# programador.net
KiCad netlist of a schematic drawn in EAGLE
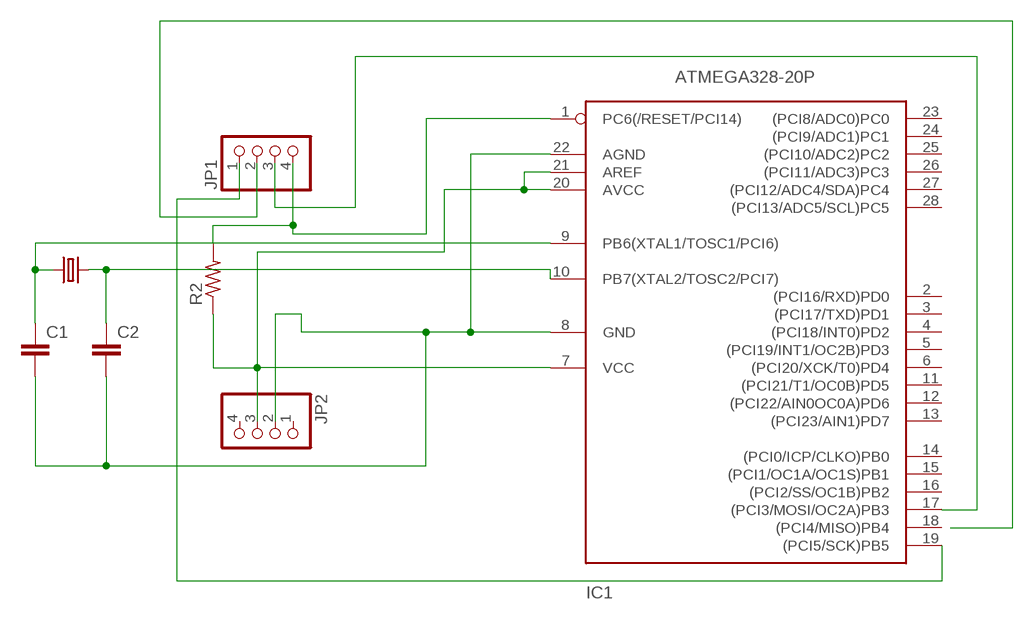
[diagram p0: schematic, sheet 1]

(export (version "E")
  (design (tool "Eeschema 10.0.6"))
  (components
    (comp (ref "C1")
      (value "C5/3.5")
      (footprint "eagle-import:C5B3.5")
      (libsource (lib "eagle-import") (part "C5/3.5"))
    )
    (comp (ref "C2")
      (value "C5/3.5")
      (footprint "eagle-import:C5B3.5")
      (libsource (lib "eagle-import") (part "C5/3.5"))
    )
    (comp (ref "IC1")
      (value "ATMEGA328-20P")
      (footprint "eagle-import:DIL28-3")
      (libsource (lib "eagle-import") (part "ATMEGA328P-20"))
    )
    (comp (ref "JP1")
      (value "PINHD-1X4")
      (footprint "eagle-import:1X04")
      (libsource (lib "eagle-import") (part "PINHD-1X4"))
    )
    (comp (ref "JP2")
      (value "PINHD-1X4")
      (footprint "eagle-import:1X04")
      (libsource (lib "eagle-import") (part "PINHD-1X4"))
    )
    (comp (ref "Q1")
      (value "CRYSTALHC49S")
      (footprint "eagle-import:HC49_S")
      (libsource (lib "eagle-import") (part "CRYSTALHC49S"))
    )
    (comp (ref "R2")
      (value "R-US_0207/10")
      (footprint "eagle-import:0207_10")
      (libsource (lib "eagle-import") (part "R-US_0207/10"))
    )
  )
  (nets
    (net (code "1") (name "Net-(IC1-(PCI3{slash}MOSI{slash}OC2A)PB3)") (class "Default")
      (node (ref "IC1") (pin "17") (pinfunction "(PCI3/MOSI/OC2A)PB3_17") (pintype "bidirectional"))
      (node (ref "JP1") (pin "3") (pinfunction "3_3") (pintype "passive"))
    )
    (net (code "2") (name "Net-(IC1-(PCI5{slash}SCK)PB5)") (class "Default")
      (node (ref "IC1") (pin "19") (pinfunction "(PCI5/SCK)PB5_19") (pintype "bidirectional"))
      (node (ref "JP1") (pin "1") (pinfunction "1_1") (pintype "passive"))
    )
    (net (code "3") (name "Net-(IC1-AGND)") (class "Default")
      (node (ref "C1") (pin "2") (pinfunction "2_2") (pintype "passive"))
      (node (ref "C2") (pin "2") (pinfunction "2_2") (pintype "passive"))
      (node (ref "IC1") (pin "22") (pinfunction "AGND_22") (pintype "bidirectional"))
      (node (ref "IC1") (pin "8") (pinfunction "GND_8") (pintype "bidirectional"))
      (node (ref "JP2") (pin "2") (pinfunction "2_2") (pintype "passive"))
    )
    (net (code "4") (name "Net-(IC1-AREF)") (class "Default")
      (node (ref "IC1") (pin "20") (pinfunction "AVCC_20") (pintype "bidirectional"))
      (node (ref "IC1") (pin "21") (pinfunction "AREF_21") (pintype "bidirectional"))
      (node (ref "IC1") (pin "7") (pinfunction "VCC_7") (pintype "bidirectional"))
      (node (ref "JP2") (pin "3") (pinfunction "3_3") (pintype "passive"))
      (node (ref "R2") (pin "1") (pinfunction "1_1") (pintype "passive"))
    )
    (net (code "5") (name "Net-(IC1-PB6(XTAL1{slash}TOSC1{slash}PCI6))") (class "Default")
      (node (ref "C1") (pin "1") (pinfunction "1_1") (pintype "passive"))
      (node (ref "IC1") (pin "9") (pinfunction "PB6(XTAL1/TOSC1/PCI6)_9") (pintype "bidirectional"))
      (node (ref "Q1") (pin "1") (pinfunction "1_1") (pintype "passive"))
    )
    (net (code "6") (name "Net-(IC1-PB7(XTAL2{slash}TOSC2{slash}PCI7))") (class "Default")
      (node (ref "C2") (pin "1") (pinfunction "1_1") (pintype "passive"))
      (node (ref "IC1") (pin "10") (pinfunction "PB7(XTAL2/TOSC2/PCI7)_10") (pintype "bidirectional"))
      (node (ref "Q1") (pin "2") (pinfunction "2_2") (pintype "passive"))
    )
    (net (code "7") (name "Net-(IC1-PC6({slash}RESET{slash}PCI14))") (class "Default")
      (node (ref "IC1") (pin "1") (pinfunction "PC6(/RESET/PCI14)_1") (pintype "bidirectional"))
      (node (ref "JP1") (pin "4") (pinfunction "4_4") (pintype "passive"))
      (node (ref "R2") (pin "2") (pinfunction "2_2") (pintype "passive"))
    )
    (net (code "8") (name "unconnected-(IC1-(PCI0{slash}ICP{slash}CLKO)PB0-Pad14)") (class "Default")
      (node (ref "IC1") (pin "14") (pinfunction "(PCI0/ICP/CLKO)PB0_14") (pintype "bidirectional"))
    )
    (net (code "9") (name "unconnected-(IC1-(PCI1{slash}OC1A{slash}OC1S)PB1-Pad15)") (class "Default")
      (node (ref "IC1") (pin "15") (pinfunction "(PCI1/OC1A/OC1S)PB1_15") (pintype "bidirectional"))
    )
    (net (code "10") (name "unconnected-(IC1-(PCI2{slash}SS{slash}OC1B)PB2-Pad16)") (class "Default")
      (node (ref "IC1") (pin "16") (pinfunction "(PCI2/SS/OC1B)PB2_16") (pintype "bidirectional"))
    )
    (net (code "11") (name "unconnected-(IC1-(PCI4{slash}MISO)PB4-Pad18)") (class "Default")
      (node (ref "IC1") (pin "18") (pinfunction "(PCI4/MISO)PB4_18") (pintype "bidirectional"))
    )
    (net (code "12") (name "unconnected-(IC1-(PCI8{slash}ADC0)PC0-Pad23)") (class "Default")
      (node (ref "IC1") (pin "23") (pinfunction "(PCI8/ADC0)PC0_23") (pintype "bidirectional"))
    )
    (net (code "13") (name "unconnected-(IC1-(PCI9{slash}ADC1)PC1-Pad24)") (class "Default")
      (node (ref "IC1") (pin "24") (pinfunction "(PCI9/ADC1)PC1_24") (pintype "bidirectional"))
    )
    (net (code "14") (name "unconnected-(IC1-(PCI10{slash}ADC2)PC2-Pad25)") (class "Default")
      (node (ref "IC1") (pin "25") (pinfunction "(PCI10/ADC2)PC2_25") (pintype "bidirectional"))
    )
    (net (code "15") (name "unconnected-(IC1-(PCI11{slash}ADC3)PC3-Pad26)") (class "Default")
      (node (ref "IC1") (pin "26") (pinfunction "(PCI11/ADC3)PC3_26") (pintype "bidirectional"))
    )
    (net (code "16") (name "unconnected-(IC1-(PCI12{slash}ADC4{slash}SDA)PC4-Pad27)") (class "Default")
      (node (ref "IC1") (pin "27") (pinfunction "(PCI12/ADC4/SDA)PC4_27") (pintype "bidirectional"))
    )
    (net (code "17") (name "unconnected-(IC1-(PCI13{slash}ADC5{slash}SCL)PC5-Pad28)") (class "Default")
      (node (ref "IC1") (pin "28") (pinfunction "(PCI13/ADC5/SCL)PC5_28") (pintype "bidirectional"))
    )
    (net (code "18") (name "unconnected-(IC1-(PCI16{slash}RXD)PD0-Pad2)") (class "Default")
      (node (ref "IC1") (pin "2") (pinfunction "(PCI16/RXD)PD0_2") (pintype "bidirectional"))
    )
    (net (code "19") (name "unconnected-(IC1-(PCI17{slash}TXD)PD1-Pad3)") (class "Default")
      (node (ref "IC1") (pin "3") (pinfunction "(PCI17/TXD)PD1_3") (pintype "bidirectional"))
    )
    (net (code "20") (name "unconnected-(IC1-(PCI18{slash}INT0)PD2-Pad4)") (class "Default")
      (node (ref "IC1") (pin "4") (pinfunction "(PCI18/INT0)PD2_4") (pintype "bidirectional"))
    )
    (net (code "21") (name "unconnected-(IC1-(PCI19{slash}INT1{slash}OC2B)PD3-Pad5)") (class "Default")
      (node (ref "IC1") (pin "5") (pinfunction "(PCI19/INT1/OC2B)PD3_5") (pintype "bidirectional"))
    )
    (net (code "22") (name "unconnected-(IC1-(PCI20{slash}XCK{slash}T0)PD4-Pad6)") (class "Default")
      (node (ref "IC1") (pin "6") (pinfunction "(PCI20/XCK/T0)PD4_6") (pintype "bidirectional"))
    )
    (net (code "23") (name "unconnected-(IC1-(PCI21{slash}T1{slash}OC0B)PD5-Pad11)") (class "Default")
      (node (ref "IC1") (pin "11") (pinfunction "(PCI21/T1/OC0B)PD5_11") (pintype "bidirectional"))
    )
    (net (code "24") (name "unconnected-(IC1-(PCI22{slash}AIN0OC0A)PD6-Pad12)") (class "Default")
      (node (ref "IC1") (pin "12") (pinfunction "(PCI22/AIN0OC0A)PD6_12") (pintype "bidirectional"))
    )
    (net (code "25") (name "unconnected-(IC1-(PCI23{slash}AIN1)PD7-Pad13)") (class "Default")
      (node (ref "IC1") (pin "13") (pinfunction "(PCI23/AIN1)PD7_13") (pintype "bidirectional"))
    )
    (net (code "26") (name "unconnected-(JP1-Pad2)") (class "Default")
      (node (ref "JP1") (pin "2") (pinfunction "2_2") (pintype "passive"))
    )
    (net (code "27") (name "unconnected-(JP2-Pad1)") (class "Default")
      (node (ref "JP2") (pin "1") (pinfunction "1_1") (pintype "passive"))
    )
    (net (code "28") (name "unconnected-(JP2-Pad4)") (class "Default")
      (node (ref "JP2") (pin "4") (pinfunction "4_4") (pintype "passive"))
    )
  )
)
